# Glint-Module.net
KiCad netlist of a schematic drawn in EAGLE
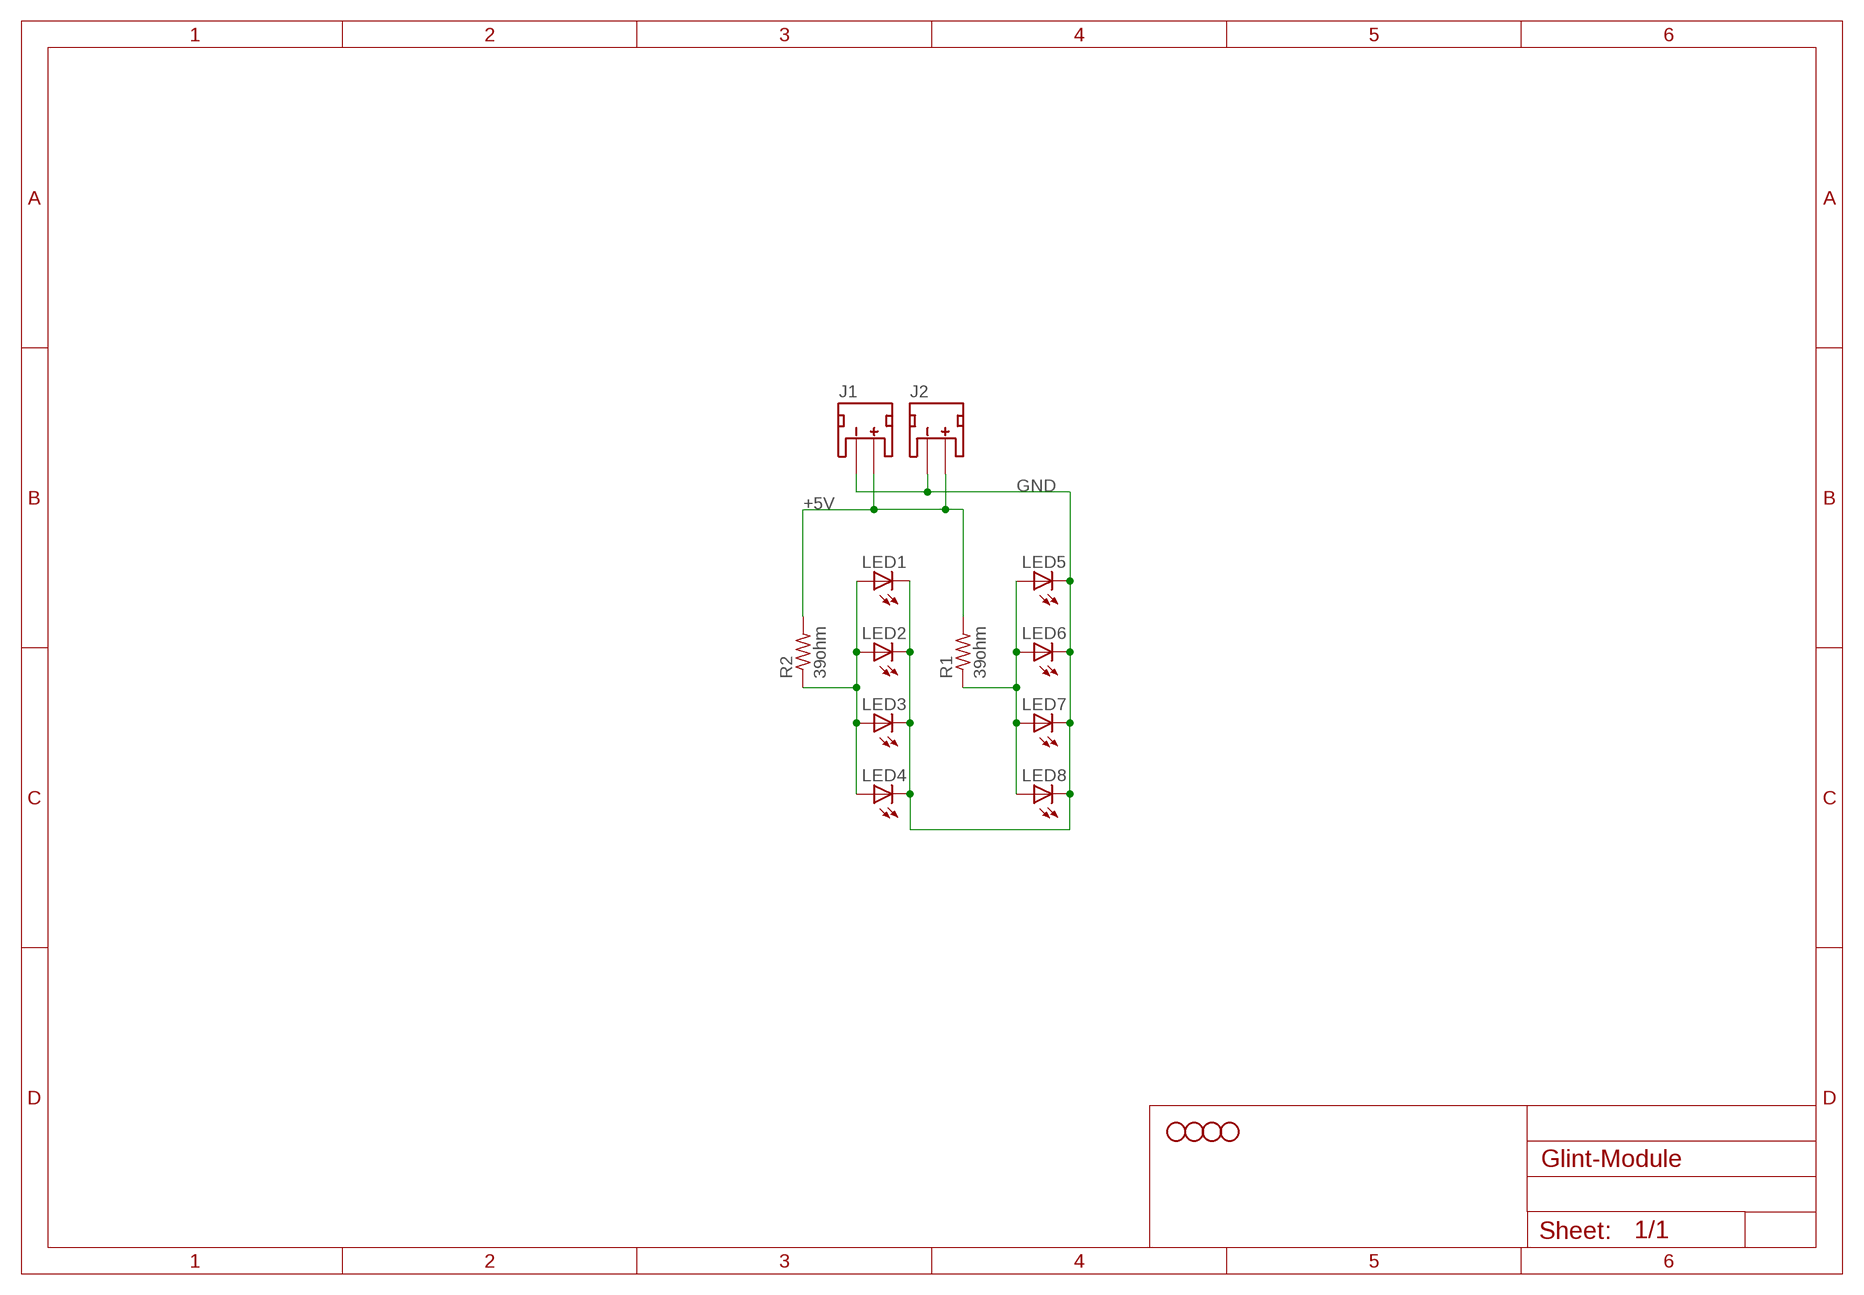
[diagram p0: schematic, sheet 1]

(export (version "E")
  (design (tool "Eeschema 10.0.6"))
  (components
    (comp (ref "J1")
      (value "JST_2MM_MALE")
      (footprint "eagle-import:JST-2-SMD")
      (libsource (lib "eagle-import") (part "JST_2MM_MALE"))
    )
    (comp (ref "J2")
      (value "JST_2MM_MALE")
      (footprint "eagle-import:JST-2-SMD")
      (libsource (lib "eagle-import") (part "JST_2MM_MALE"))
    )
    (comp (ref "LED1")
      (value "LED5MM")
      (footprint "eagle-import:LED5MM")
      (libsource (lib "eagle-import") (part "LED5MM"))
    )
    (comp (ref "LED2")
      (value "LED5MM")
      (footprint "eagle-import:LED5MM")
      (libsource (lib "eagle-import") (part "LED5MM"))
    )
    (comp (ref "LED3")
      (value "LED5MM")
      (footprint "eagle-import:LED5MM")
      (libsource (lib "eagle-import") (part "LED5MM"))
    )
    (comp (ref "LED4")
      (value "LED5MM")
      (footprint "eagle-import:LED5MM")
      (libsource (lib "eagle-import") (part "LED5MM"))
    )
    (comp (ref "LED5")
      (value "LED5MM")
      (footprint "eagle-import:LED5MM")
      (libsource (lib "eagle-import") (part "LED5MM"))
    )
    (comp (ref "LED6")
      (value "LED5MM")
      (footprint "eagle-import:LED5MM")
      (libsource (lib "eagle-import") (part "LED5MM"))
    )
    (comp (ref "LED7")
      (value "LED5MM")
      (footprint "eagle-import:LED5MM")
      (libsource (lib "eagle-import") (part "LED5MM"))
    )
    (comp (ref "LED8")
      (value "LED5MM")
      (footprint "eagle-import:LED5MM")
      (libsource (lib "eagle-import") (part "LED5MM"))
    )
    (comp (ref "R1")
      (value "39ohm")
      (footprint "eagle-import:0309_10")
      (libsource (lib "eagle-import") (part "R-US_0309/10"))
    )
    (comp (ref "R2")
      (value "39ohm")
      (footprint "eagle-import:0309_10")
      (libsource (lib "eagle-import") (part "R-US_0309/10"))
    )
    (comp (ref "STANDOFF1")
      (value "STAND-OFF")
      (footprint "eagle-import:STAND-OFF")
      (libsource (lib "eagle-import") (part "STAND-OFF"))
    )
    (comp (ref "STANDOFF2")
      (value "STAND-OFF")
      (footprint "eagle-import:STAND-OFF")
      (libsource (lib "eagle-import") (part "STAND-OFF"))
    )
    (comp (ref "STANDOFF3")
      (value "STAND-OFF")
      (footprint "eagle-import:STAND-OFF")
      (libsource (lib "eagle-import") (part "STAND-OFF"))
    )
    (comp (ref "STANDOFF4")
      (value "STAND-OFF")
      (footprint "eagle-import:STAND-OFF")
      (libsource (lib "eagle-import") (part "STAND-OFF"))
    )
  )
  (nets
    (net (code "1") (name "/+5V") (class "Default")
      (node (ref "J1") (pin "2") (pinfunction "+_2") (pintype "bidirectional"))
      (node (ref "J2") (pin "2") (pinfunction "+_2") (pintype "bidirectional"))
      (node (ref "R1") (pin "2") (pinfunction "2_2") (pintype "passive"))
      (node (ref "R2") (pin "2") (pinfunction "2_2") (pintype "passive"))
    )
    (net (code "2") (name "/GND") (class "Default")
      (node (ref "J1") (pin "1") (pinfunction "-_1") (pintype "bidirectional"))
      (node (ref "J2") (pin "1") (pinfunction "-_1") (pintype "bidirectional"))
      (node (ref "LED1") (pin "K") (pinfunction "C_K") (pintype "passive"))
      (node (ref "LED2") (pin "K") (pinfunction "C_K") (pintype "passive"))
      (node (ref "LED3") (pin "K") (pinfunction "C_K") (pintype "passive"))
      (node (ref "LED4") (pin "K") (pinfunction "C_K") (pintype "passive"))
      (node (ref "LED5") (pin "K") (pinfunction "C_K") (pintype "passive"))
      (node (ref "LED6") (pin "K") (pinfunction "C_K") (pintype "passive"))
      (node (ref "LED7") (pin "K") (pinfunction "C_K") (pintype "passive"))
      (node (ref "LED8") (pin "K") (pinfunction "C_K") (pintype "passive"))
    )
    (net (code "3") (name "Net-(LED1-PadA)") (class "Default")
      (node (ref "LED1") (pin "A") (pinfunction "A_A") (pintype "passive"))
      (node (ref "LED2") (pin "A") (pinfunction "A_A") (pintype "passive"))
      (node (ref "LED3") (pin "A") (pinfunction "A_A") (pintype "passive"))
      (node (ref "LED4") (pin "A") (pinfunction "A_A") (pintype "passive"))
      (node (ref "R2") (pin "1") (pinfunction "1_1") (pintype "passive"))
    )
    (net (code "4") (name "Net-(LED5-PadA)") (class "Default")
      (node (ref "LED5") (pin "A") (pinfunction "A_A") (pintype "passive"))
      (node (ref "LED6") (pin "A") (pinfunction "A_A") (pintype "passive"))
      (node (ref "LED7") (pin "A") (pinfunction "A_A") (pintype "passive"))
      (node (ref "LED8") (pin "A") (pinfunction "A_A") (pintype "passive"))
      (node (ref "R1") (pin "1") (pinfunction "1_1") (pintype "passive"))
    )
    (net (code "5") (name "unconnected-(J1-PAD1-PadNC1)") (class "Default")
      (node (ref "J1") (pin "NC1") (pinfunction "PAD1_NC1") (pintype "bidirectional"))
    )
    (net (code "6") (name "unconnected-(J1-PAD2-PadNC2)") (class "Default")
      (node (ref "J1") (pin "NC2") (pinfunction "PAD2_NC2") (pintype "bidirectional"))
    )
    (net (code "7") (name "unconnected-(J2-PAD1-PadNC1)") (class "Default")
      (node (ref "J2") (pin "NC1") (pinfunction "PAD1_NC1") (pintype "bidirectional"))
    )
    (net (code "8") (name "unconnected-(J2-PAD2-PadNC2)") (class "Default")
      (node (ref "J2") (pin "NC2") (pinfunction "PAD2_NC2") (pintype "bidirectional"))
    )
  )
)
